# Coolant_Relays.net
KiCad netlist of a schematic drawn in Altium Designer
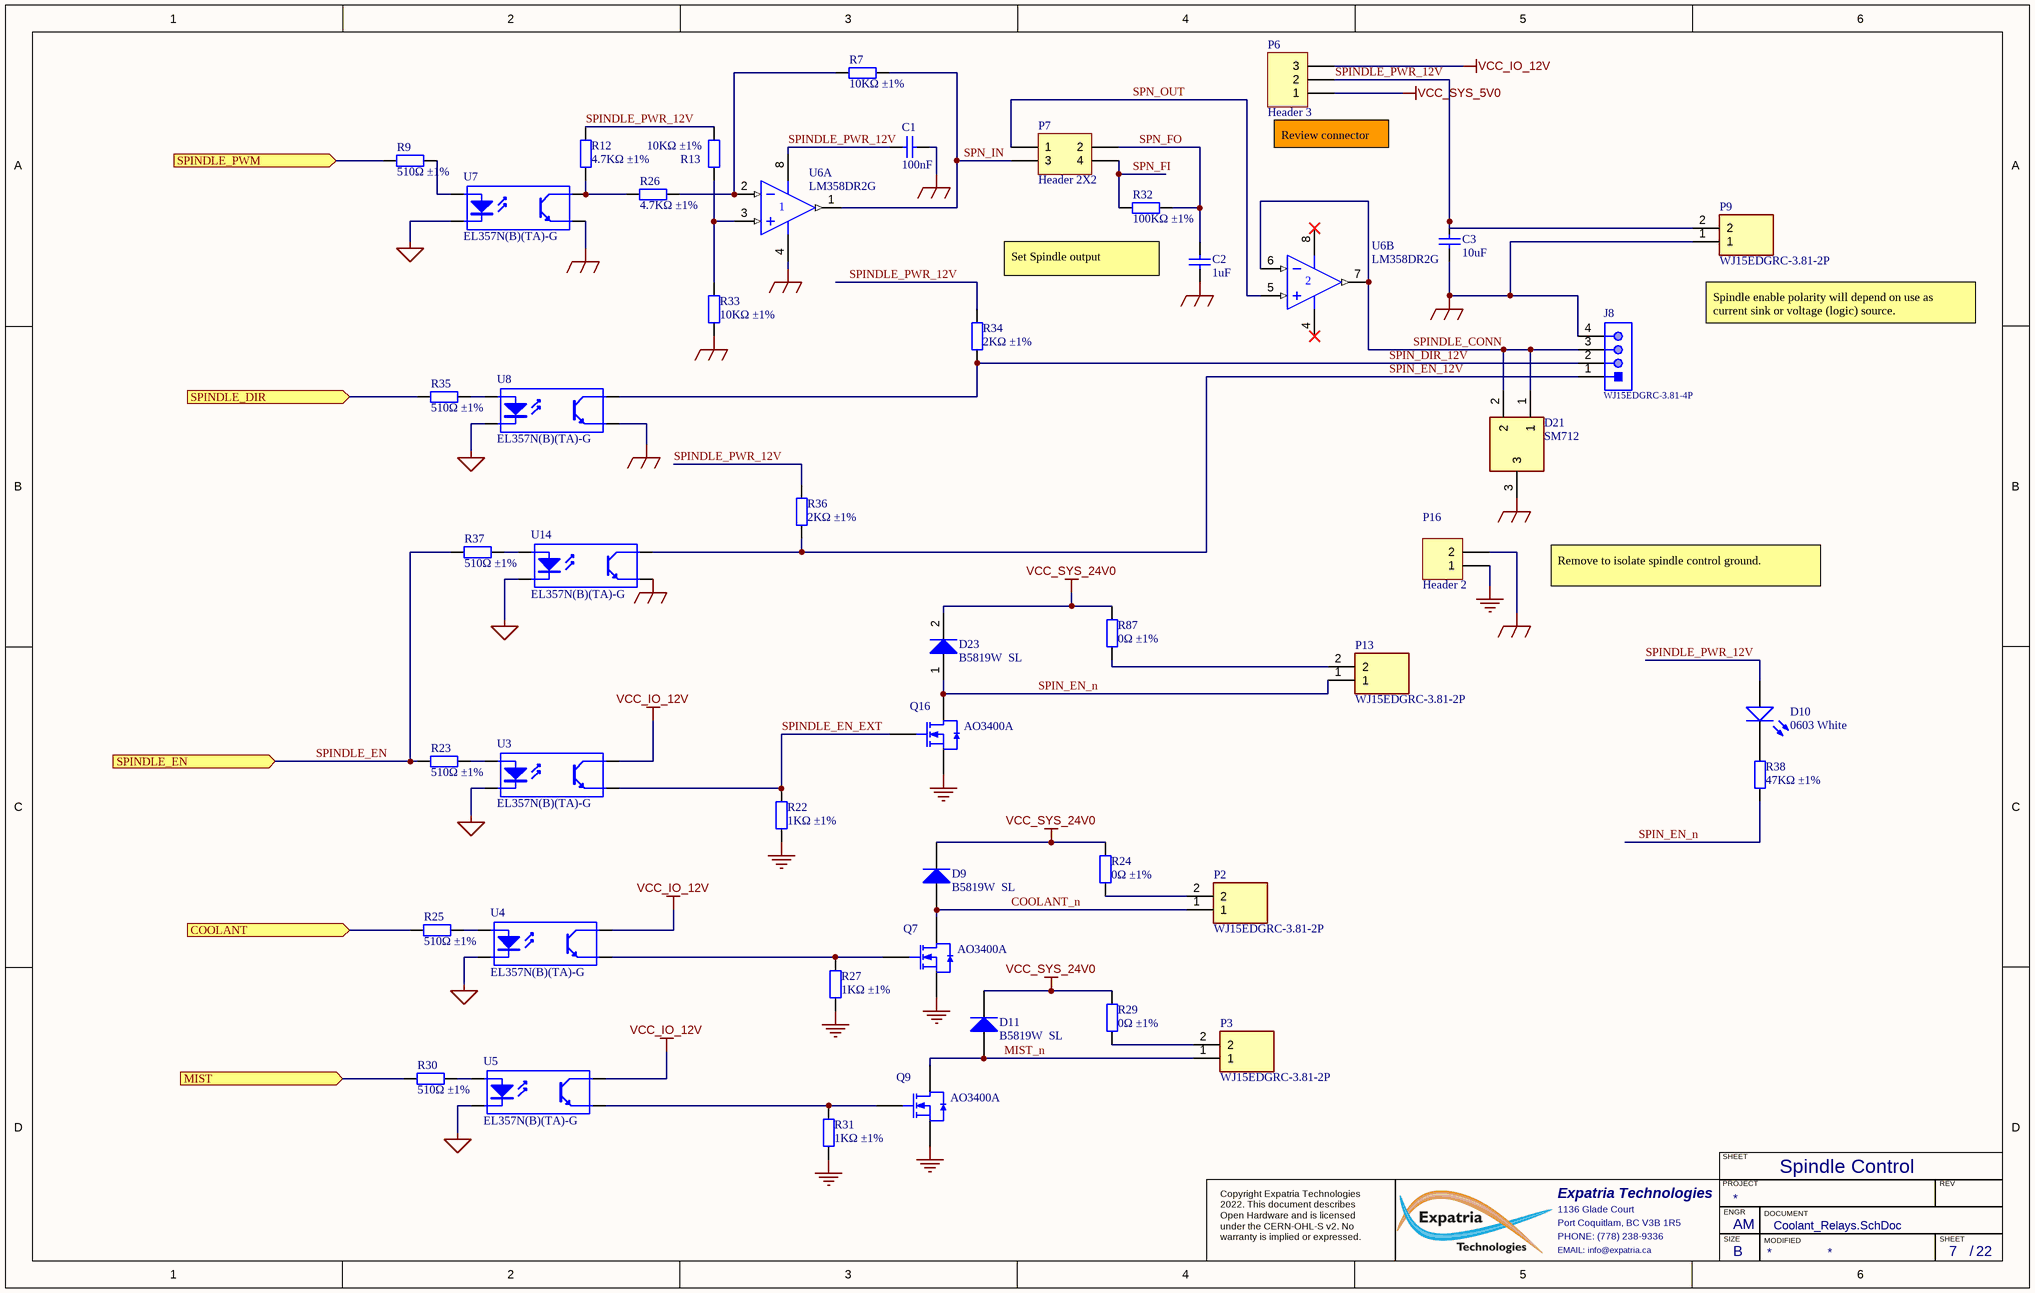
[diagram p0: Coolant_Relays.SchDoc]

(export (version "E")
  (design (tool "Eeschema 10.0.6"))
  (components
    (comp (ref "C1")
      (value "100nF")
      (footprint "0603_C")
      (description "Chip capacitors")
      (fields (field (name "MANUFACTURER") "YAGEO") (field (name "PARTNUMBER") "CC0603KRX7R9BB104"))
      (libsource (lib "Cap") (part "0603 100nF (104) 10% 50V"))
    )
    (comp (ref "C2")
      (value "1uF")
      (footprint "0603_C")
      (description "Chip capacitors")
      (fields
        (field (name "MANUFACTURER") "Samsung Electro-Mechanics")
        (field (name "PARTNUMBER") "CL10A105KB8NNNC")
      )
      (libsource (lib "Cap") (part "0603 1uF (105) 10% 50V"))
    )
    (comp (ref "C3")
      (value "10uF")
      (footprint "1206_C")
      (description "Chip capacitors")
      (fields
        (field (name "MANUFACTURER") "Samsung Electro-Mechanics")
        (field (name "PARTNUMBER") "CL31A106KBHNNNE")
      )
      (libsource (lib "Cap") (part "1206 10uF (106) 10% 50V"))
    )
    (comp (ref "D9")
      (value "B5819W  SL")
      (footprint "SOD-123")
      (description "Schottky Diode")
      (libsource (lib "Diode") (part "SOD-123 B5819W  SL"))
    )
    (comp (ref "D10")
      (value "0603 White")
      (footprint "0603_LED_S1")
      (description "LED")
      (libsource (lib "Sienci_Labs") (part "19-217UWD/S365-2/TR8"))
    )
    (comp (ref "D11")
      (value "B5819W  SL")
      (footprint "SOD-123")
      (description "Schottky Diode")
      (libsource (lib "Diode") (part "SOD-123 B5819W  SL"))
    )
    (comp (ref "D21")
      (value "SM712")
      (footprint "SamacSys:SOT95P230X117-3N")
      (description "Bidirectional 12V (Max), 7V (Max) 7.5V / 13.3V 10V / 20V 12A(8/20us) SOT-23-3 TVS RoHS")
      (libsource (lib "*") (part "CDSOT23-SM712"))
    )
    (comp (ref "D23")
      (value "B5819W  SL")
      (footprint "SOD-123")
      (description "Schottky Diode")
      (libsource (lib "") (part "SOD-123 B5819W  SL_1"))
    )
    (comp (ref "J8")
      (value "WJ15EDGRC-3.81-4P")
      (footprint "SHDRRA4W85P0X381_1X4_1612X915X720P")
      (description "3.81mm Green Board Edge/Receptacle-Close Push-Pull,P=3.81mm Pluggable System Terminal Block ROHS")
      (fields (field (name "MANUFACTURER") "Ningbo Kangnex Elec"))
      (libsource (lib "Sienci_Labs") (part "WJ15EDGRC-3.81-4P"))
    )
    (comp (ref "P2")
      (value "WJ15EDGRC-3.81-2P")
      (footprint "SHDRRA2W85P0X381_1X2_850X915X720P")
      (description "3.81mm Green Board Edge/Receptacle-Close Push-Pull,P=3.81mm Pluggable System Terminal Block ROHS")
      (libsource (lib "Sienci_Labs") (part "WJ15EDGRC-3.81-2P"))
    )
    (comp (ref "P3")
      (value "WJ15EDGRC-3.81-2P")
      (footprint "SHDRRA2W85P0X381_1X2_850X915X720P")
      (description "3.81mm Green Board Edge/Receptacle-Close Push-Pull,P=3.81mm Pluggable System Terminal Block ROHS")
      (libsource (lib "Sienci_Labs") (part "WJ15EDGRC-3.81-2P"))
    )
    (comp (ref "P6")
      (value "Header 3")
      (footprint "HDR1X3")
      (description "Header, 3-Pin")
      (fields (field (name "PUBLISHER") "Altium Limited"))
      (libsource (lib "Miscellaneous Connectors") (part "Header 3"))
    )
    (comp (ref "P7")
      (value "Header 2X2")
      (footprint "HDR2X2")
      (description "Header, 2-Pin, Dual row")
      (libsource (lib "Miscellaneous Connectors") (part "Header 2X2"))
    )
    (comp (ref "P9")
      (value "WJ15EDGRC-3.81-2P")
      (footprint "SHDRRA2W85P0X381_1X2_850X915X720P")
      (description "3.81mm Green Board Edge/Receptacle-Close Push-Pull,P=3.81mm Pluggable System Terminal Block ROHS")
      (libsource (lib "Sienci_Labs") (part "WJ15EDGRC-3.81-2P"))
    )
    (comp (ref "P13")
      (value "WJ15EDGRC-3.81-2P")
      (footprint "SHDRRA2W85P0X381_1X2_850X915X720P")
      (description "3.81mm Green Board Edge/Receptacle-Close Push-Pull,P=3.81mm Pluggable System Terminal Block ROHS")
      (libsource (lib "Sienci_Labs") (part "WJ15EDGRC-3.81-2P"))
    )
    (comp (ref "P16")
      (value "Header 2")
      (footprint "HDR1X2")
      (description "Header, 2-Pin")
      (fields (field (name "PUBLISHER") "Altium Limited"))
      (libsource (lib "Miscellaneous Connectors") (part "Header 2"))
    )
    (comp (ref "Q7")
      (value "AO3400A")
      (footprint "SOT-23-3L")
      (description "MOSFET N-CH 30V 5.7A SOT23-3L")
      (libsource (lib "Sienci_Labs") (part "AO3400A"))
    )
    (comp (ref "Q9")
      (value "AO3400A")
      (footprint "SOT-23-3L")
      (description "MOSFET N-CH 30V 5.7A SOT23-3L")
      (libsource (lib "Sienci_Labs") (part "AO3400A"))
    )
    (comp (ref "Q16")
      (value "AO3400A")
      (footprint "SOT-23-3L")
      (description "MOSFET N-CH 30V 5.7A SOT23-3L")
      (libsource (lib "Sienci_Labs") (part "AO3400A"))
    )
    (comp (ref "R7")
      (value "10KΩ ±1%")
      (footprint "0603_R")
      (description "Chip resistor")
      (fields (field (name "MANUFACTURER") "Uniroyal Elec") (field (name "PARTNUMBER") "0603WAF1002T5E"))
      (libsource (lib "") (part "0603 10K (1002) 1%_1"))
    )
    (comp (ref "R9")
      (value "510Ω ±1%")
      (footprint "0603_R")
      (description "Chip resistor")
      (fields (field (name "MANUFACTURER") "Uniroyal Elec") (field (name "PARTNUMBER") "0603WAF5100T5E"))
      (libsource (lib "RES") (part "0603 510R (5100) 1%"))
    )
    (comp (ref "R12")
      (value "4.7KΩ ±1%")
      (footprint "0603_R")
      (description "Chip resistor")
      (fields (field (name "MANUFACTURER") "Uniroyal Elec") (field (name "PARTNUMBER") "0603WAF4701T5E"))
      (libsource (lib "") (part "0603 4.7K (4701) 1%_1"))
    )
    (comp (ref "R13")
      (value "10KΩ ±1%")
      (footprint "0603_R")
      (description "Chip resistor")
      (fields (field (name "MANUFACTURER") "Uniroyal Elec") (field (name "PARTNUMBER") "0603WAF1002T5E"))
      (libsource (lib "RES") (part "0603 10K (1002) 1%"))
    )
    (comp (ref "R22")
      (value "1KΩ ±1%")
      (footprint "0603_R")
      (description "Chip resistor")
      (fields (field (name "MANUFACTURER") "Uniroyal Elec") (field (name "PARTNUMBER") "0603WAF1001T5E"))
      (libsource (lib "RES") (part "0603 1K (1001) 1%"))
    )
    (comp (ref "R23")
      (value "510Ω ±1%")
      (footprint "0603_R")
      (description "Chip resistor")
      (fields (field (name "MANUFACTURER") "Uniroyal Elec") (field (name "PARTNUMBER") "0603WAF5100T5E"))
      (libsource (lib "RES") (part "0603 510R (5100) 1%"))
    )
    (comp (ref "R24")
      (value "0Ω ±1%")
      (footprint "0603_R")
      (description "Chip resistor")
      (fields (field (name "MANUFACTURER") "Uniroyal Elec") (field (name "PARTNUMBER") "0603WAF0000T5E"))
      (libsource (lib "RES") (part "0603 0R (0R0) 1%"))
    )
    (comp (ref "R25")
      (value "510Ω ±1%")
      (footprint "0603_R")
      (description "Chip resistor")
      (fields (field (name "MANUFACTURER") "Uniroyal Elec") (field (name "PARTNUMBER") "0603WAF5100T5E"))
      (libsource (lib "RES") (part "0603 510R (5100) 1%"))
    )
    (comp (ref "R26")
      (value "4.7KΩ ±1%")
      (footprint "0603_R")
      (description "Chip resistor")
      (fields (field (name "MANUFACTURER") "Uniroyal Elec") (field (name "PARTNUMBER") "0603WAF4701T5E"))
      (libsource (lib "RES") (part "0603 4.7K (4701) 1%"))
    )
    (comp (ref "R27")
      (value "1KΩ ±1%")
      (footprint "0603_R")
      (description "Chip resistor")
      (fields (field (name "MANUFACTURER") "Uniroyal Elec") (field (name "PARTNUMBER") "0603WAF1001T5E"))
      (libsource (lib "RES") (part "0603 1K (1001) 1%"))
    )
    (comp (ref "R29")
      (value "0Ω ±1%")
      (footprint "0603_R")
      (description "Chip resistor")
      (fields (field (name "MANUFACTURER") "Uniroyal Elec") (field (name "PARTNUMBER") "0603WAF0000T5E"))
      (libsource (lib "RES") (part "0603 0R (0R0) 1%"))
    )
    (comp (ref "R30")
      (value "510Ω ±1%")
      (footprint "0603_R")
      (description "Chip resistor")
      (fields (field (name "MANUFACTURER") "Uniroyal Elec") (field (name "PARTNUMBER") "0603WAF5100T5E"))
      (libsource (lib "RES") (part "0603 510R (5100) 1%"))
    )
    (comp (ref "R31")
      (value "1KΩ ±1%")
      (footprint "0603_R")
      (description "Chip resistor")
      (fields (field (name "MANUFACTURER") "Uniroyal Elec") (field (name "PARTNUMBER") "0603WAF1001T5E"))
      (libsource (lib "RES") (part "0603 1K (1001) 1%"))
    )
    (comp (ref "R32")
      (value "100KΩ ±1%")
      (footprint "0603_R")
      (description "Chip resistor")
      (fields (field (name "MANUFACTURER") "Uniroyal Elec") (field (name "PARTNUMBER") "0603WAF1003T5E"))
      (libsource (lib "RES") (part "0603 100K (1003) 1%"))
    )
    (comp (ref "R33")
      (value "10KΩ ±1%")
      (footprint "0603_R")
      (description "Chip resistor")
      (fields (field (name "MANUFACTURER") "Uniroyal Elec") (field (name "PARTNUMBER") "0603WAF1002T5E"))
      (libsource (lib "RES") (part "0603 10K (1002) 1%"))
    )
    (comp (ref "R34")
      (value "2KΩ ±1%")
      (footprint "0603_R")
      (description "Chip resistor")
      (fields (field (name "MANUFACTURER") "Uniroyal Elec") (field (name "PARTNUMBER") "0603WAF2001T5E"))
      (libsource (lib "RES") (part "0603 2K (2001) 1%"))
    )
    (comp (ref "R35")
      (value "510Ω ±1%")
      (footprint "0603_R")
      (description "Chip resistor")
      (fields (field (name "MANUFACTURER") "Uniroyal Elec") (field (name "PARTNUMBER") "0603WAF5100T5E"))
      (libsource (lib "RES") (part "0603 510R (5100) 1%"))
    )
    (comp (ref "R36")
      (value "2KΩ ±1%")
      (footprint "0603_R")
      (description "Chip resistor")
      (fields (field (name "MANUFACTURER") "Uniroyal Elec") (field (name "PARTNUMBER") "0603WAF2001T5E"))
      (libsource (lib "RES") (part "0603 2K (2001) 1%"))
    )
    (comp (ref "R37")
      (value "510Ω ±1%")
      (footprint "0603_R")
      (description "Chip resistor")
      (fields (field (name "MANUFACTURER") "Uniroyal Elec") (field (name "PARTNUMBER") "0603WAF5100T5E"))
      (libsource (lib "RES") (part "0603 510R (5100) 1%"))
    )
    (comp (ref "R38")
      (value "47KΩ ±1%")
      (footprint "0603_R")
      (description "Chip resistor")
      (fields (field (name "MANUFACTURER") "Uniroyal Elec") (field (name "PARTNUMBER") "0603WAF4702T5E"))
      (libsource (lib "RES") (part "0603 47K (4702) 1%"))
    )
    (comp (ref "R87")
      (value "0Ω ±1%")
      (footprint "0603_R")
      (description "Chip resistor")
      (fields (field (name "MANUFACTURER") "Uniroyal Elec") (field (name "PARTNUMBER") "0603WAF0000T5E"))
      (libsource (lib "RES") (part "0603 0R (0R0) 1%"))
    )
    (comp (ref "U3")
      (value "EL357N(B)(TA)-G")
      (footprint "Miscellaneous Devices LC:SOP-4_P2.54")
      (description "OPTOISOLATOR 3.75KV TRANS 4-SOP")
      (libsource (lib "IC") (part "EL357N(B)(TA)-G_[C6649]"))
    )
    (comp (ref "U4")
      (value "EL357N(B)(TA)-G")
      (footprint "Miscellaneous Devices LC:SOP-4_P2.54")
      (description "OPTOISOLATOR 3.75KV TRANS 4-SOP")
      (libsource (lib "IC") (part "EL357N(B)(TA)-G_[C6649]"))
    )
    (comp (ref "U5")
      (value "EL357N(B)(TA)-G")
      (footprint "Miscellaneous Devices LC:SOP-4_P2.54")
      (description "OPTOISOLATOR 3.75KV TRANS 4-SOP")
      (libsource (lib "IC") (part "EL357N(B)(TA)-G_[C6649]"))
    )
    (comp (ref "U6")
      (value "LM358DR2G")
      (footprint "SOIC-8_150mil")
      (description "Dual Op Amp,  5 - 28 V,  8-PinSOIC")
      (libsource (lib "PrintNC_GRBLHAL_Breakout") (part "LM358DR2G_[C7950]"))
    )
    (comp (ref "U7")
      (value "EL357N(B)(TA)-G")
      (footprint "Miscellaneous Devices LC:SOP-4_P2.54")
      (description "OPTOISOLATOR 3.75KV TRANS 4-SOP")
      (libsource (lib "PrintNC_GRBLHAL_Breakout") (part "EL357N(B)(TA)-G_[C6649]"))
    )
    (comp (ref "U8")
      (value "EL357N(B)(TA)-G")
      (footprint "Miscellaneous Devices LC:SOP-4_P2.54")
      (description "OPTOISOLATOR 3.75KV TRANS 4-SOP")
      (libsource (lib "PrintNC_GRBLHAL_Breakout") (part "EL357N(B)(TA)-G_[C6649]"))
    )
    (comp (ref "U14")
      (value "EL357N(B)(TA)-G")
      (footprint "Miscellaneous Devices LC:SOP-4_P2.54")
      (description "OPTOISOLATOR 3.75KV TRANS 4-SOP")
      (libsource (lib "PrintNC_GRBLHAL_Breakout") (part "EL357N(B)(TA)-G_[C6649]"))
    )
  )
  (nets
    (net (code "1") (name "/COOLANT") (class "Default")
      (node (ref "R25") (pin "1") (pinfunction "1_1") (pintype "passive"))
    )
    (net (code "2") (name "/COOLANT_n") (class "Default")
      (node (ref "D9") (pin "1") (pinfunction "A_1") (pintype "passive"))
      (node (ref "P2") (pin "1") (pinfunction "1_1") (pintype "passive"))
      (node (ref "Q7") (pin "3") (pinfunction "D_3") (pintype "passive"))
    )
    (net (code "3") (name "/MIST") (class "Default")
      (node (ref "R30") (pin "1") (pinfunction "1_1") (pintype "passive"))
    )
    (net (code "4") (name "/MIST_n") (class "Default")
      (node (ref "D11") (pin "1") (pinfunction "A_1") (pintype "passive"))
      (node (ref "P3") (pin "1") (pinfunction "1_1") (pintype "passive"))
      (node (ref "Q9") (pin "3") (pinfunction "D_3") (pintype "passive"))
    )
    (net (code "5") (name "/SPINDLE_CONN") (class "Default")
      (node (ref "D21") (pin "1") (pinfunction "1_1") (pintype "passive"))
      (node (ref "D21") (pin "2") (pinfunction "2_2") (pintype "passive"))
      (node (ref "J8") (pin "3") (pinfunction "3_3") (pintype "passive"))
      (node (ref "U6") (pin "6") (pinfunction "IN-_6") (pintype "input"))
      (node (ref "U6") (pin "7") (pinfunction "OUT_7") (pintype "output"))
    )
    (net (code "6") (name "/SPINDLE_DIR") (class "Default")
      (node (ref "R35") (pin "1") (pinfunction "1_1") (pintype "passive"))
    )
    (net (code "7") (name "/SPINDLE_EN") (class "Default")
      (node (ref "R23") (pin "1") (pinfunction "1_1") (pintype "passive"))
      (node (ref "R37") (pin "1") (pinfunction "1_1") (pintype "passive"))
    )
    (net (code "8") (name "/SPINDLE_EN_EXT") (class "Default")
      (node (ref "Q16") (pin "1") (pinfunction "G_1") (pintype "passive"))
      (node (ref "R22") (pin "2") (pinfunction "2_2") (pintype "passive"))
      (node (ref "U3") (pin "3") (pinfunction "E_3") (pintype "passive"))
    )
    (net (code "9") (name "/SPINDLE_PWM") (class "Default")
      (node (ref "R9") (pin "1") (pinfunction "1_1") (pintype "passive"))
    )
    (net (code "10") (name "/SPINDLE_PWR_12V") (class "Default")
      (node (ref "C1") (pin "2") (pinfunction "2_2") (pintype "passive"))
      (node (ref "C3") (pin "2") (pinfunction "2_2") (pintype "passive"))
      (node (ref "D10") (pin "A") (pinfunction "A_A") (pintype "passive"))
      (node (ref "P6") (pin "2") (pinfunction "2_2") (pintype "passive"))
      (node (ref "P9") (pin "2") (pinfunction "2_2") (pintype "passive"))
      (node (ref "R12") (pin "1") (pinfunction "1_1") (pintype "passive"))
      (node (ref "R13") (pin "1") (pinfunction "1_1") (pintype "passive"))
      (node (ref "R34") (pin "2") (pinfunction "2_2") (pintype "passive"))
      (node (ref "R36") (pin "2") (pinfunction "2_2") (pintype "passive"))
      (node (ref "U6") (pin "8") (pinfunction "V+_8") (pintype "power_in"))
    )
    (net (code "11") (name "/SPIN_DIR_12V") (class "Default")
      (node (ref "J8") (pin "2") (pinfunction "2_2") (pintype "passive"))
      (node (ref "R34") (pin "1") (pinfunction "1_1") (pintype "passive"))
      (node (ref "U8") (pin "4") (pinfunction "C_4") (pintype "passive"))
    )
    (net (code "12") (name "/SPIN_EN_12V") (class "Default")
      (node (ref "J8") (pin "1") (pinfunction "1_1") (pintype "passive"))
      (node (ref "R36") (pin "1") (pinfunction "1_1") (pintype "passive"))
      (node (ref "U14") (pin "4") (pinfunction "C_4") (pintype "passive"))
    )
    (net (code "13") (name "/SPIN_EN_n") (class "Default")
      (node (ref "D23") (pin "1") (pinfunction "A_1") (pintype "passive"))
      (node (ref "P13") (pin "1") (pinfunction "1_1") (pintype "passive"))
      (node (ref "Q16") (pin "3") (pinfunction "D_3") (pintype "passive"))
      (node (ref "R38") (pin "1") (pinfunction "1_1") (pintype "passive"))
    )
    (net (code "14") (name "/SPN_FI") (class "Default")
      (node (ref "P7") (pin "4") (pinfunction "4_4") (pintype "passive"))
      (node (ref "R32") (pin "2") (pinfunction "2_2") (pintype "passive"))
    )
    (net (code "15") (name "/SPN_FO") (class "Default")
      (node (ref "C2") (pin "2") (pinfunction "2_2") (pintype "passive"))
      (node (ref "P7") (pin "2") (pinfunction "2_2") (pintype "passive"))
      (node (ref "R32") (pin "1") (pinfunction "1_1") (pintype "passive"))
    )
    (net (code "16") (name "/SPN_IN") (class "Default")
      (node (ref "P7") (pin "3") (pinfunction "3_3") (pintype "passive"))
      (node (ref "R7") (pin "2") (pinfunction "2_2") (pintype "passive"))
      (node (ref "U6") (pin "1") (pinfunction "OUT_1") (pintype "output"))
    )
    (net (code "17") (name "/SPN_OUT") (class "Default")
      (node (ref "P7") (pin "1") (pinfunction "1_1") (pintype "passive"))
      (node (ref "U6") (pin "5") (pinfunction "IN+_5") (pintype "input"))
    )
    (net (code "18") (name "GND") (class "Default")
      (node (ref "P16") (pin "1") (pinfunction "1_1") (pintype "passive"))
      (node (ref "Q16") (pin "2") (pinfunction "S_2") (pintype "passive"))
      (node (ref "Q7") (pin "2") (pinfunction "S_2") (pintype "passive"))
      (node (ref "Q9") (pin "2") (pinfunction "S_2") (pintype "passive"))
      (node (ref "R22") (pin "1") (pinfunction "1_1") (pintype "passive"))
      (node (ref "R27") (pin "1") (pinfunction "1_1") (pintype "passive"))
      (node (ref "R31") (pin "1") (pinfunction "1_1") (pintype "passive"))
    )
    (net (code "19") (name "MCU_GND") (class "Default")
      (node (ref "U14") (pin "2") (pinfunction "K_2") (pintype "passive"))
      (node (ref "U3") (pin "2") (pinfunction "K_2") (pintype "passive"))
      (node (ref "U4") (pin "2") (pinfunction "K_2") (pintype "passive"))
      (node (ref "U5") (pin "2") (pinfunction "K_2") (pintype "passive"))
      (node (ref "U7") (pin "2") (pinfunction "K_2") (pintype "passive"))
      (node (ref "U8") (pin "2") (pinfunction "K_2") (pintype "passive"))
    )
    (net (code "20") (name "Net-(D10-PadK)") (class "Default")
      (node (ref "D10") (pin "K") (pinfunction "K_K") (pintype "passive"))
      (node (ref "R38") (pin "2") (pinfunction "2_2") (pintype "passive"))
    )
    (net (code "21") (name "Net-(P2-Pad2)") (class "Default")
      (node (ref "P2") (pin "2") (pinfunction "2_2") (pintype "passive"))
      (node (ref "R24") (pin "2") (pinfunction "2_2") (pintype "passive"))
    )
    (net (code "22") (name "Net-(P3-Pad2)") (class "Default")
      (node (ref "P3") (pin "2") (pinfunction "2_2") (pintype "passive"))
      (node (ref "R29") (pin "2") (pinfunction "2_2") (pintype "passive"))
    )
    (net (code "23") (name "Net-(P13-Pad2)") (class "Default")
      (node (ref "P13") (pin "2") (pinfunction "2_2") (pintype "passive"))
      (node (ref "R87") (pin "2") (pinfunction "2_2") (pintype "passive"))
    )
    (net (code "24") (name "Net-(Q7-G)") (class "Default")
      (node (ref "Q7") (pin "1") (pinfunction "G_1") (pintype "passive"))
      (node (ref "R27") (pin "2") (pinfunction "2_2") (pintype "passive"))
      (node (ref "U4") (pin "3") (pinfunction "E_3") (pintype "passive"))
    )
    (net (code "25") (name "Net-(Q9-G)") (class "Default")
      (node (ref "Q9") (pin "1") (pinfunction "G_1") (pintype "passive"))
      (node (ref "R31") (pin "2") (pinfunction "2_2") (pintype "passive"))
      (node (ref "U5") (pin "3") (pinfunction "E_3") (pintype "passive"))
    )
    (net (code "26") (name "Net-(U3-A)") (class "Default")
      (node (ref "R23") (pin "2") (pinfunction "2_2") (pintype "passive"))
      (node (ref "U3") (pin "1") (pinfunction "A_1") (pintype "passive"))
    )
    (net (code "27") (name "Net-(U4-A)") (class "Default")
      (node (ref "R25") (pin "2") (pinfunction "2_2") (pintype "passive"))
      (node (ref "U4") (pin "1") (pinfunction "A_1") (pintype "passive"))
    )
    (net (code "28") (name "Net-(U5-A)") (class "Default")
      (node (ref "R30") (pin "2") (pinfunction "2_2") (pintype "passive"))
      (node (ref "U5") (pin "1") (pinfunction "A_1") (pintype "passive"))
    )
    (net (code "29") (name "Net-(U6A-IN+)") (class "Default")
      (node (ref "R13") (pin "2") (pinfunction "2_2") (pintype "passive"))
      (node (ref "R33") (pin "1") (pinfunction "1_1") (pintype "passive"))
      (node (ref "U6") (pin "3") (pinfunction "IN+_3") (pintype "input"))
    )
    (net (code "30") (name "Net-(U6A-IN-)") (class "Default")
      (node (ref "R26") (pin "2") (pinfunction "2_2") (pintype "passive"))
      (node (ref "R7") (pin "1") (pinfunction "1_1") (pintype "passive"))
      (node (ref "U6") (pin "2") (pinfunction "IN-_2") (pintype "input"))
    )
    (net (code "31") (name "Net-(U7-A)") (class "Default")
      (node (ref "R9") (pin "2") (pinfunction "2_2") (pintype "passive"))
      (node (ref "U7") (pin "1") (pinfunction "A_1") (pintype "passive"))
    )
    (net (code "32") (name "Net-(U7-C)") (class "Default")
      (node (ref "R12") (pin "2") (pinfunction "2_2") (pintype "passive"))
      (node (ref "R26") (pin "1") (pinfunction "1_1") (pintype "passive"))
      (node (ref "U7") (pin "4") (pinfunction "C_4") (pintype "passive"))
    )
    (net (code "33") (name "Net-(U8-A)") (class "Default")
      (node (ref "R35") (pin "2") (pinfunction "2_2") (pintype "passive"))
      (node (ref "U8") (pin "1") (pinfunction "A_1") (pintype "passive"))
    )
    (net (code "34") (name "Net-(U14-A)") (class "Default")
      (node (ref "R37") (pin "2") (pinfunction "2_2") (pintype "passive"))
      (node (ref "U14") (pin "1") (pinfunction "A_1") (pintype "passive"))
    )
    (net (code "35") (name "SPIN_GND") (class "Default")
      (node (ref "C1") (pin "1") (pinfunction "1_1") (pintype "passive"))
      (node (ref "C2") (pin "1") (pinfunction "1_1") (pintype "passive"))
      (node (ref "C3") (pin "1") (pinfunction "1_1") (pintype "passive"))
      (node (ref "D21") (pin "3") (pinfunction "3_3") (pintype "passive"))
      (node (ref "J8") (pin "4") (pinfunction "4_4") (pintype "passive"))
      (node (ref "P16") (pin "2") (pinfunction "2_2") (pintype "passive"))
      (node (ref "P9") (pin "1") (pinfunction "1_1") (pintype "passive"))
      (node (ref "R33") (pin "2") (pinfunction "2_2") (pintype "passive"))
      (node (ref "U14") (pin "3") (pinfunction "E_3") (pintype "passive"))
      (node (ref "U6") (pin "4") (pinfunction "V-_4") (pintype "power_in"))
      (node (ref "U7") (pin "3") (pinfunction "E_3") (pintype "passive"))
      (node (ref "U8") (pin "3") (pinfunction "E_3") (pintype "passive"))
    )
    (net (code "36") (name "VCC_IO_12V") (class "Default")
      (node (ref "P6") (pin "3") (pinfunction "3_3") (pintype "passive"))
      (node (ref "U3") (pin "4") (pinfunction "C_4") (pintype "passive"))
      (node (ref "U4") (pin "4") (pinfunction "C_4") (pintype "passive"))
      (node (ref "U5") (pin "4") (pinfunction "C_4") (pintype "passive"))
    )
    (net (code "37") (name "VCC_SYS_5V0") (class "Default")
      (node (ref "P6") (pin "1") (pinfunction "1_1") (pintype "passive"))
    )
    (net (code "38") (name "VCC_SYS_24V0") (class "Default")
      (node (ref "D11") (pin "2") (pinfunction "K_2") (pintype "passive"))
      (node (ref "D23") (pin "2") (pinfunction "K_2") (pintype "passive"))
      (node (ref "D9") (pin "2") (pinfunction "K_2") (pintype "passive"))
      (node (ref "R24") (pin "1") (pinfunction "1_1") (pintype "passive"))
      (node (ref "R29") (pin "1") (pinfunction "1_1") (pintype "passive"))
      (node (ref "R87") (pin "1") (pinfunction "1_1") (pintype "passive"))
    )
    (net (code "39") (name "unconnected-(U6B-V+-Pad8)") (class "Default")
      (node (ref "U6") (pin "8") (pinfunction "V+_8") (pintype "power_in+no_connect"))
    )
    (net (code "40") (name "unconnected-(U6B-V--Pad4)") (class "Default")
      (node (ref "U6") (pin "4") (pinfunction "V-_4") (pintype "power_in+no_connect"))
    )
  )
)
